# chiclet.net
KiCad netlist of a schematic drawn in EAGLE
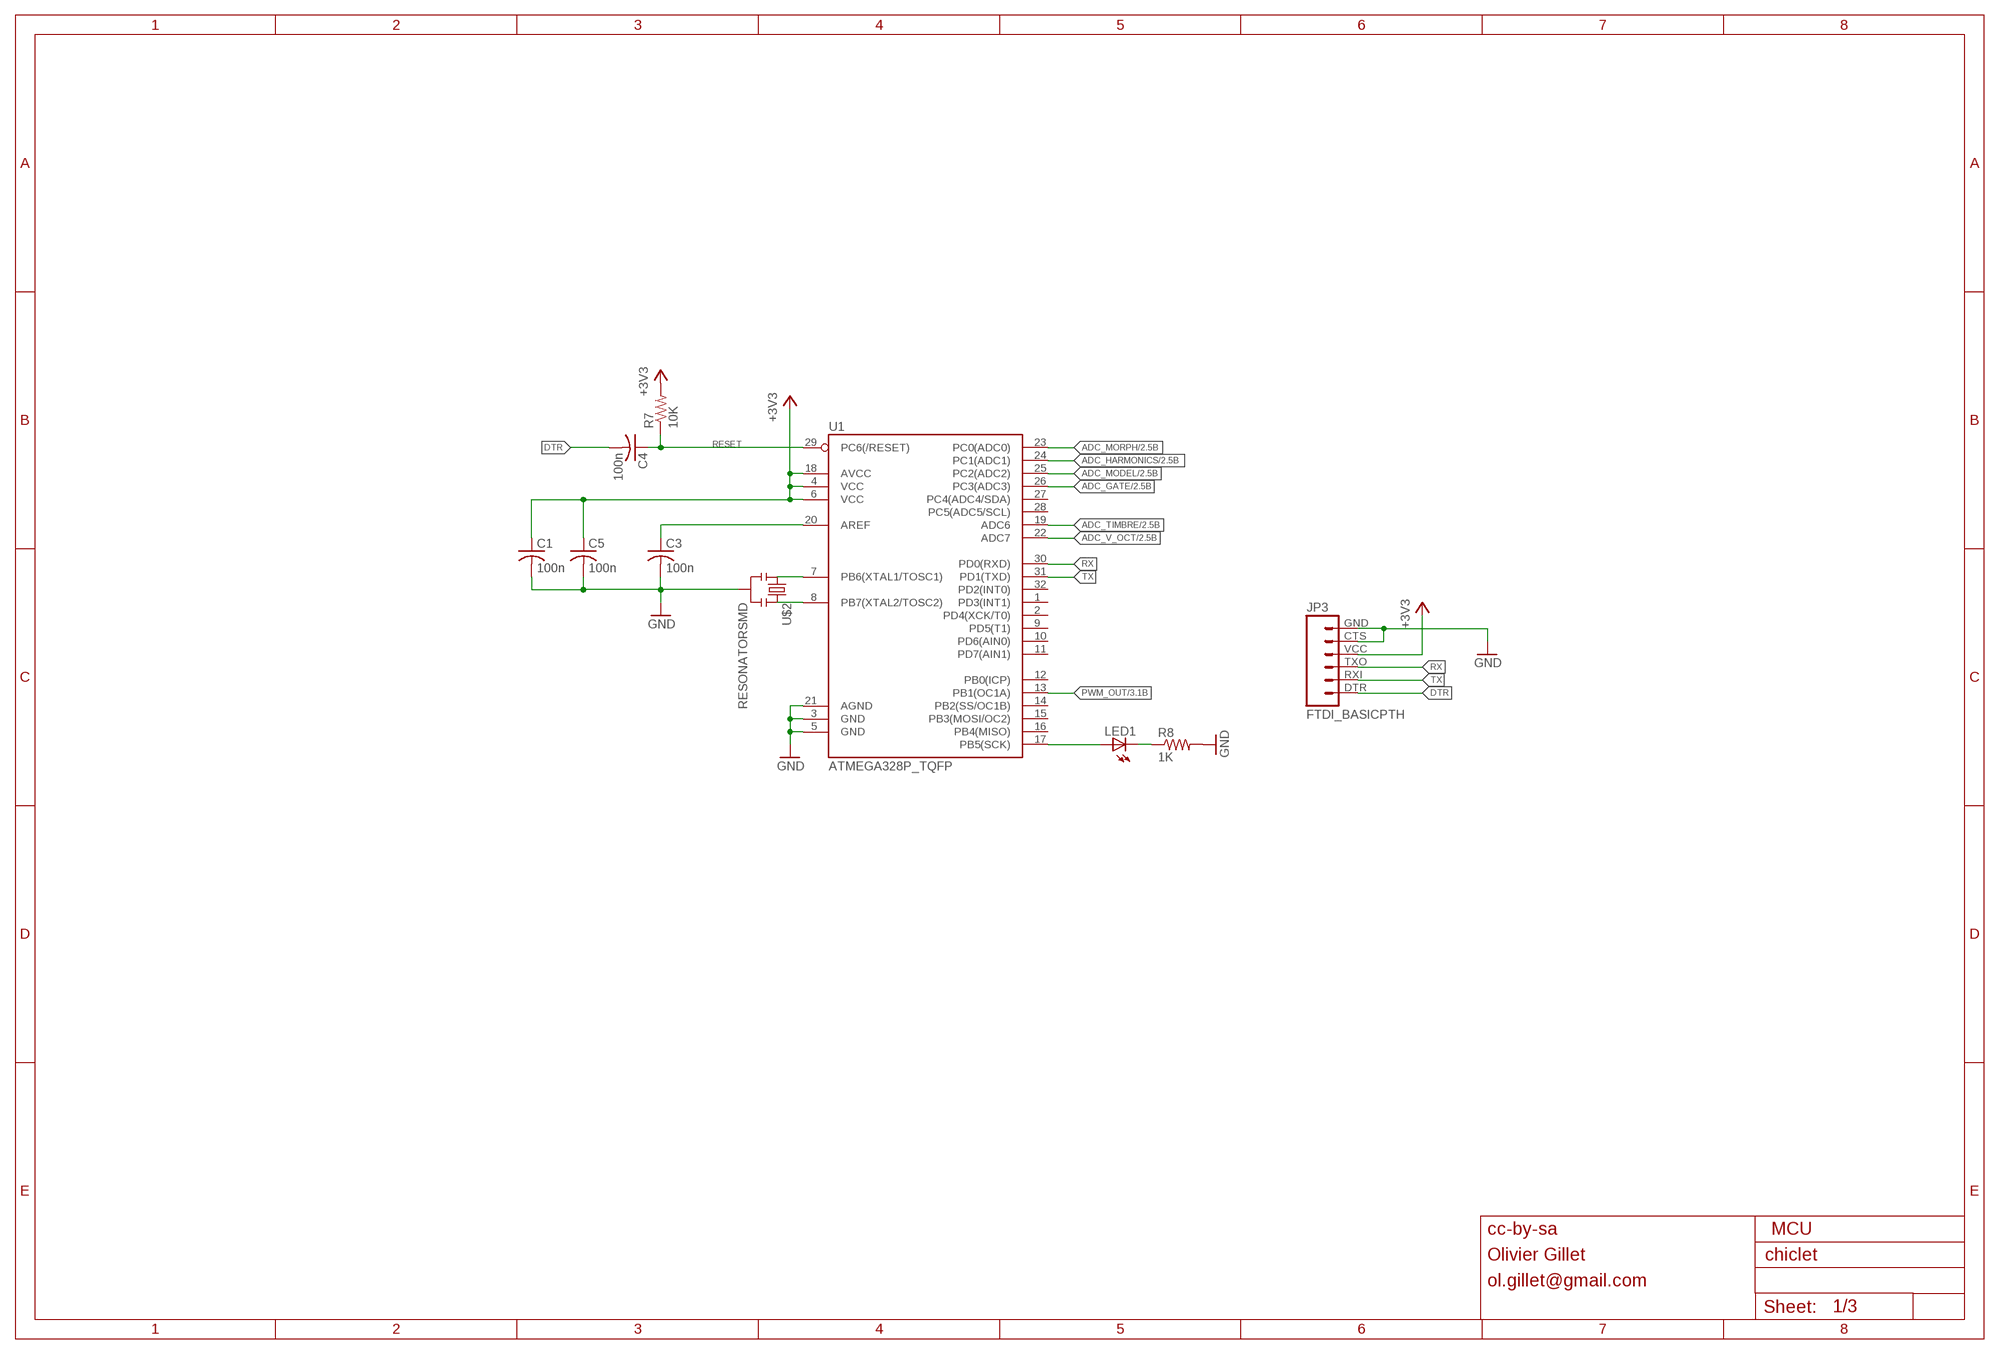
[diagram p0: schematic, sheet 1]
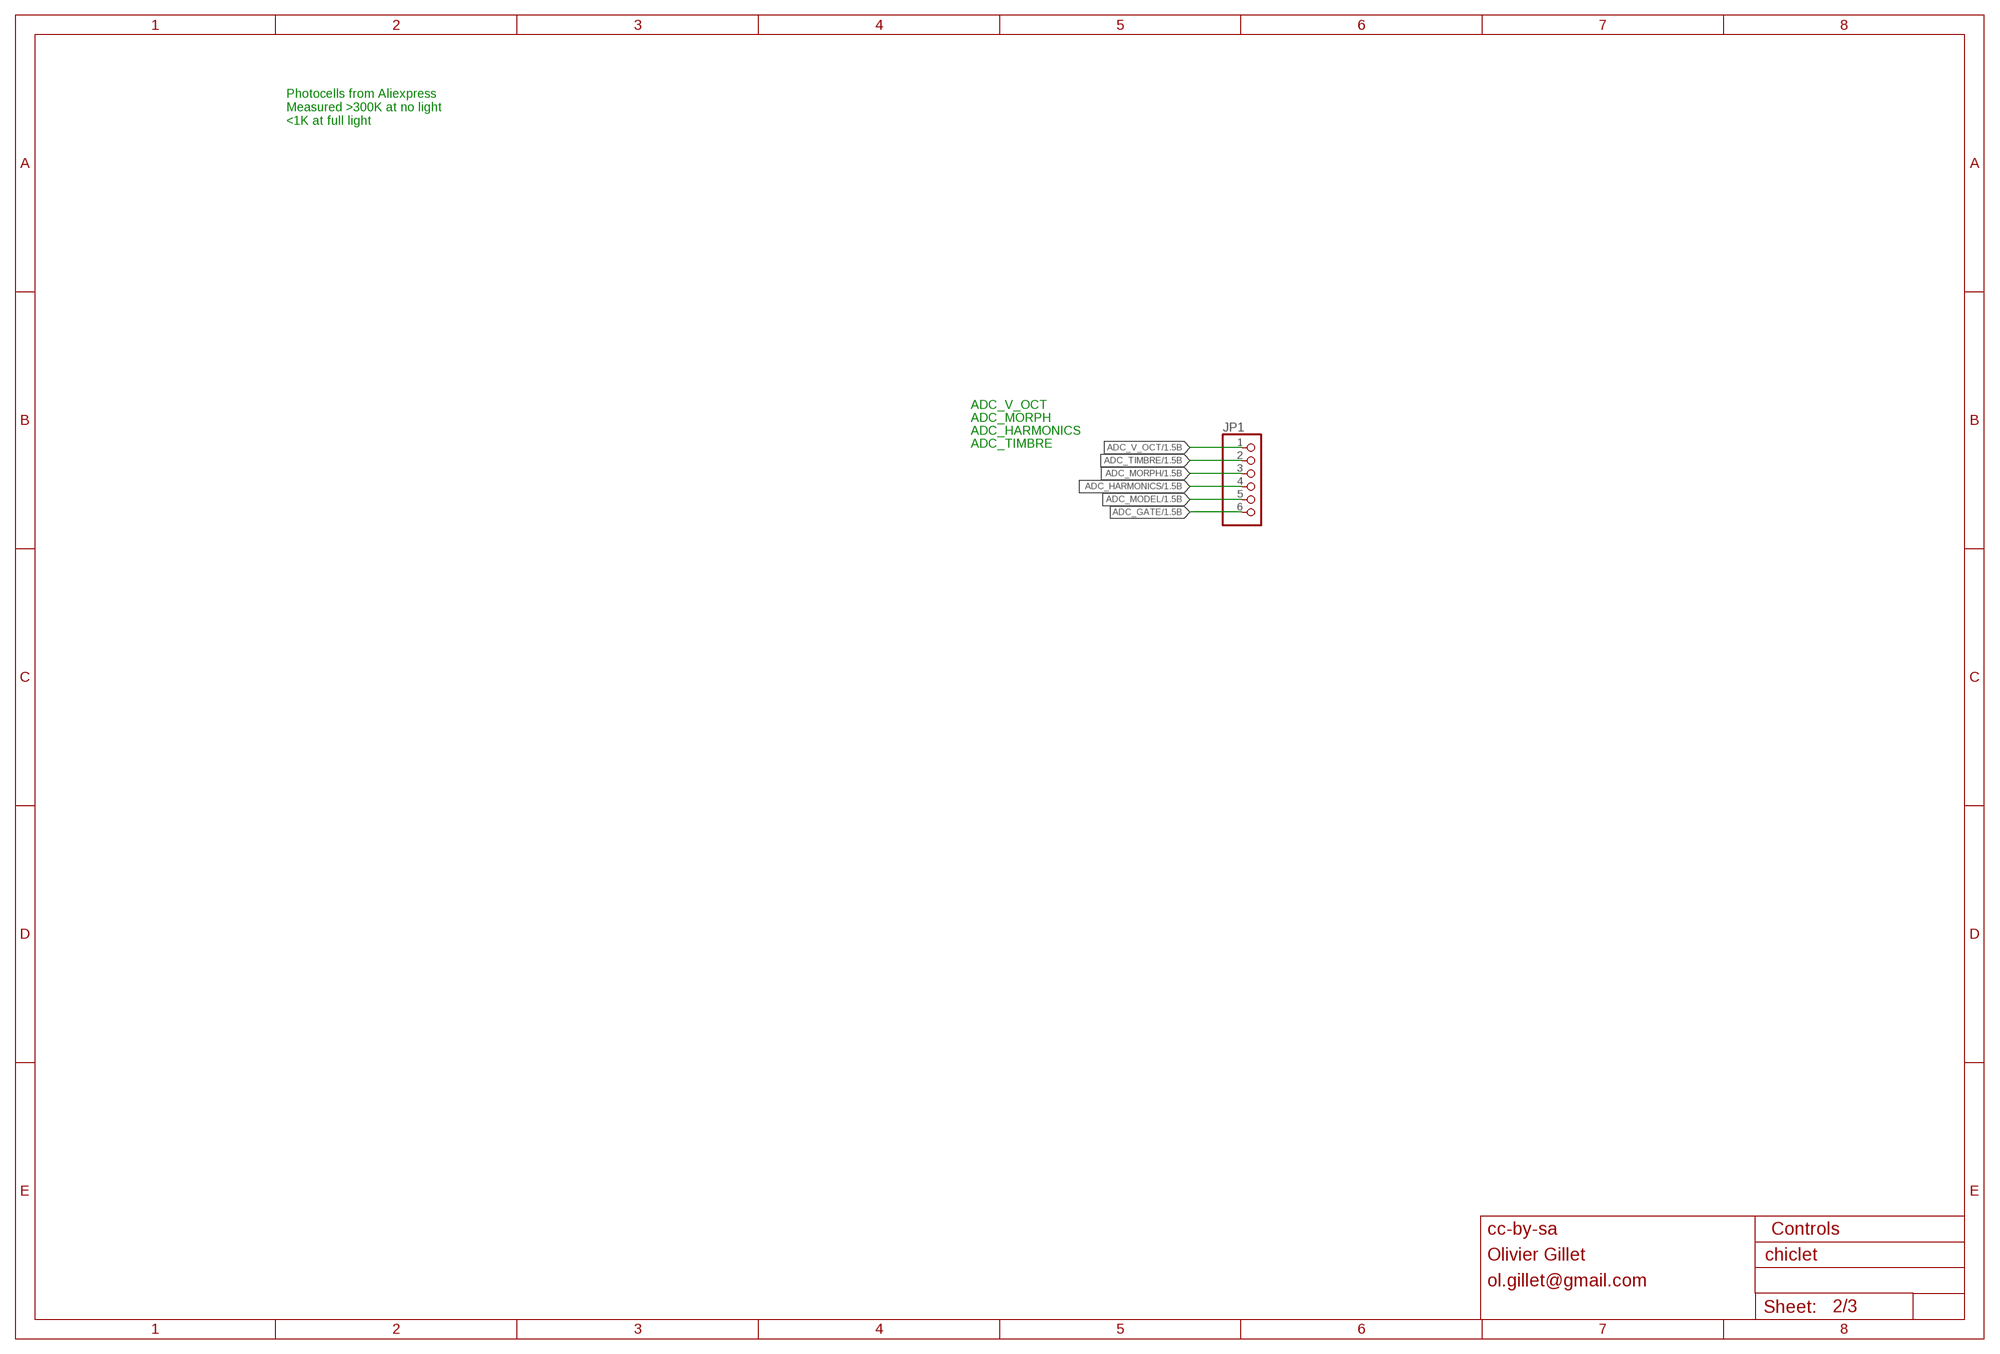
[diagram p1: schematic, sheet 2]
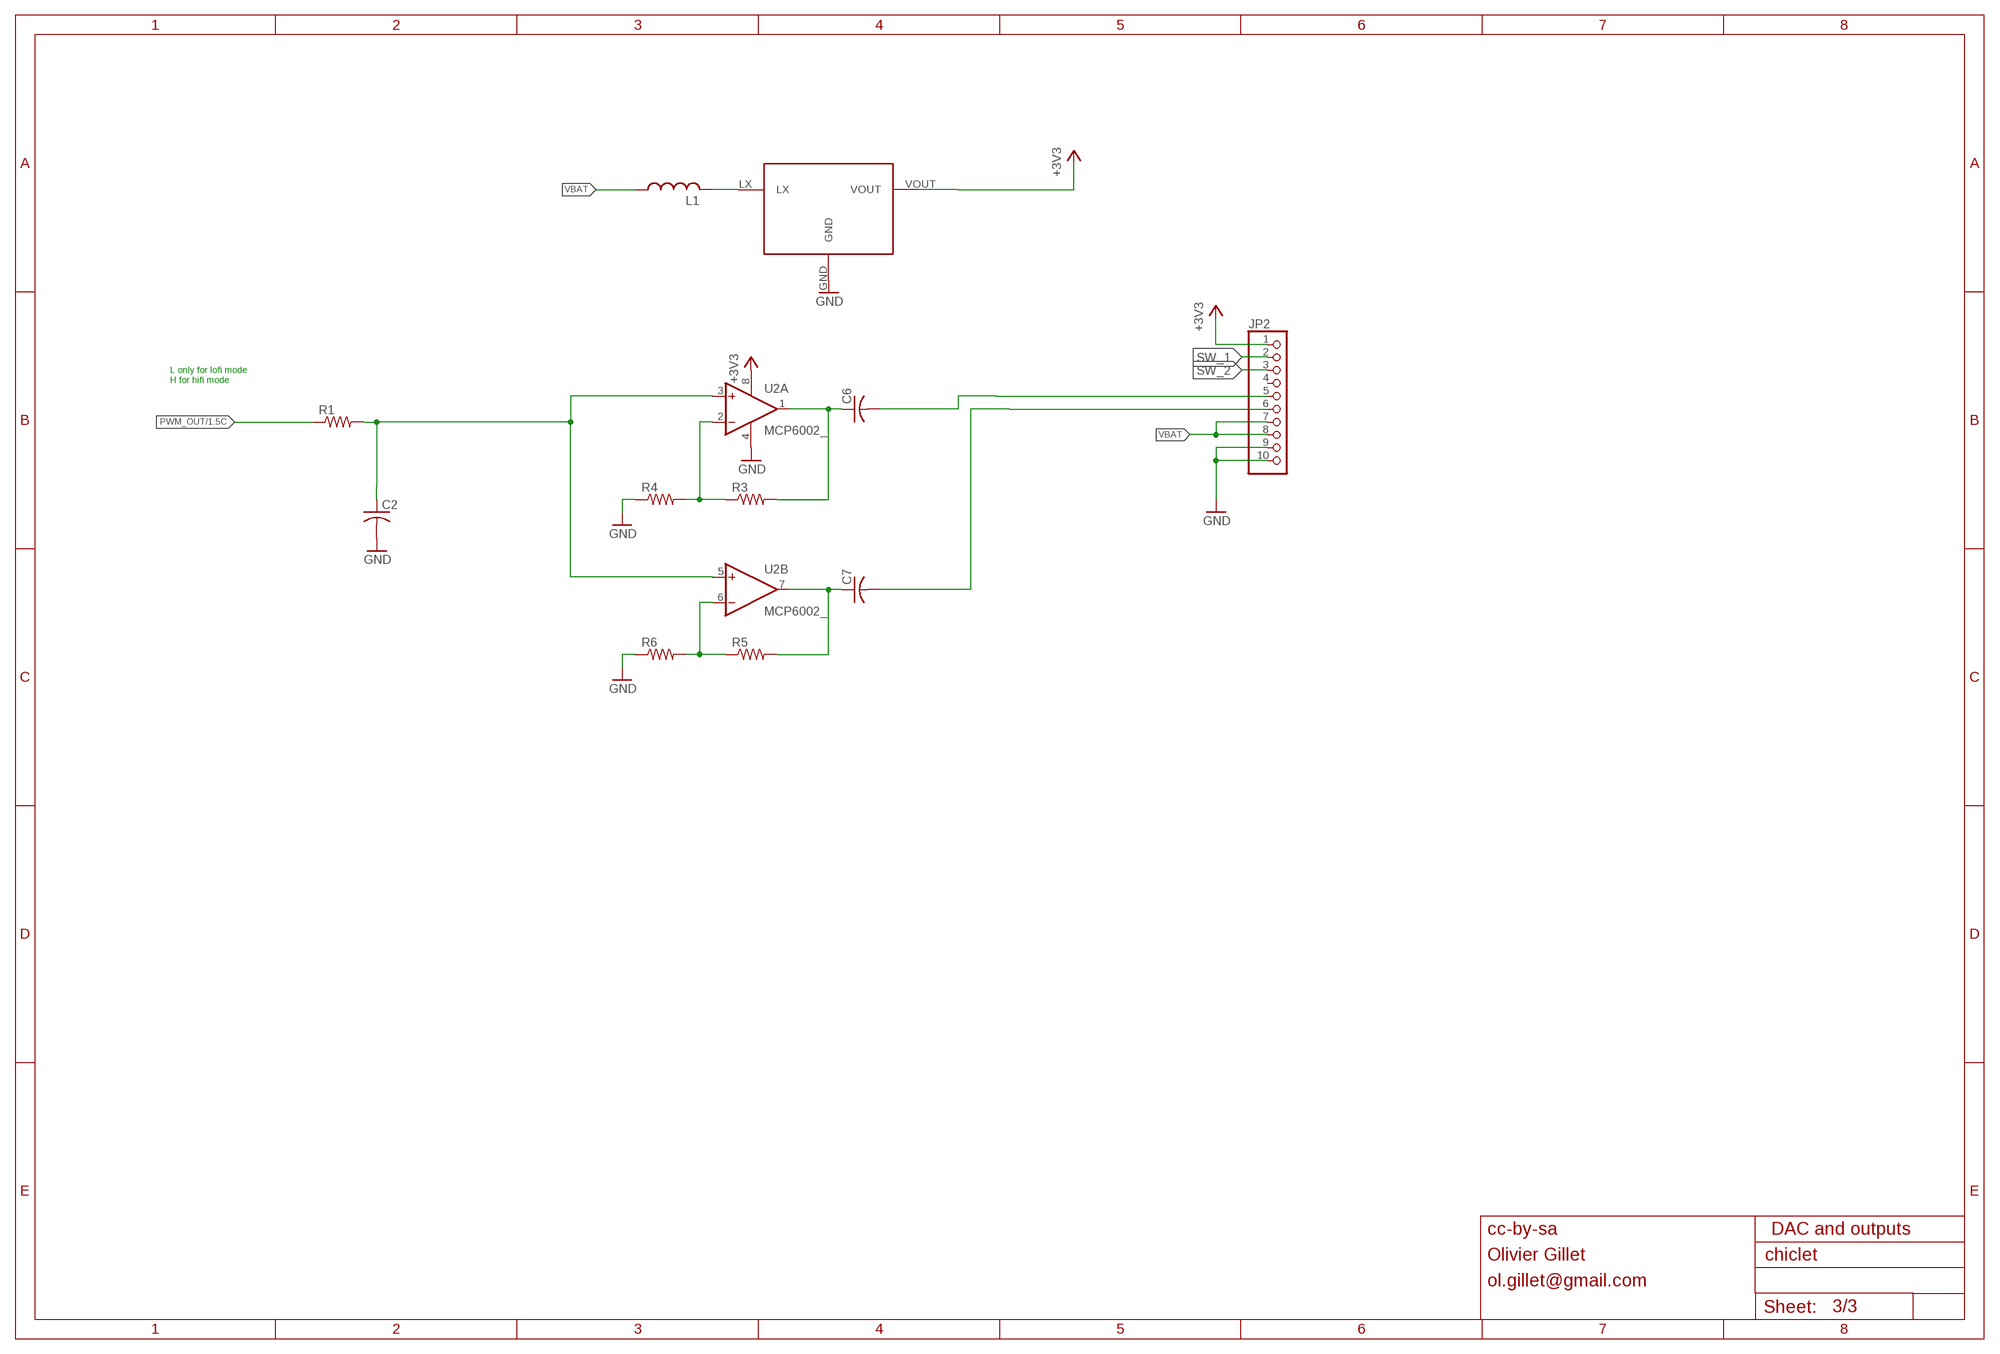
[diagram p2: schematic, sheet 3]

(export (version "E")
  (design (tool "Eeschema 10.0.6"))
  (components
    (comp (ref "C1")
      (value "100n")
      (footprint "eagle-import:C0805")
      (libsource (lib "eagle-import") (part "C-USC0805"))
    )
    (comp (ref "C3")
      (value "100n")
      (footprint "eagle-import:C0805")
      (libsource (lib "eagle-import") (part "C-USC0805"))
    )
    (comp (ref "C4")
      (value "100n")
      (footprint "eagle-import:C0805")
      (libsource (lib "eagle-import") (part "C-USC0805"))
    )
    (comp (ref "C5")
      (value "100n")
      (footprint "eagle-import:C0805")
      (libsource (lib "eagle-import") (part "C-USC0805"))
    )
    (comp (ref "JP3")
      (value "FTDI_BASICPTH")
      (footprint "eagle-import:FTDI_BASIC")
      (libsource (lib "eagle-import") (part "FTDI_BASICPTH"))
    )
    (comp (ref "LED1")
      (value "LED-0805")
      (footprint "eagle-import:LED-805")
      (libsource (lib "eagle-import") (part "LED-0805"))
    )
    (comp (ref "R7")
      (value "10K")
      (footprint "eagle-import:M0805")
      (libsource (lib "eagle-import") (part "R-US_M0805"))
    )
    (comp (ref "R8")
      (value "1K")
      (footprint "eagle-import:M0805")
      (libsource (lib "eagle-import") (part "R-US_M0805"))
    )
    (comp (ref "U$2")
      (value "RESONATORSMD")
      (footprint "eagle-import:RESONATOR-SMD")
      (libsource (lib "eagle-import") (part "RESONATORSMD"))
    )
    (comp (ref "U1")
      (value "ATMEGA328P_TQFP")
      (footprint "eagle-import:TQFP32-08")
      (libsource (lib "eagle-import") (part "ATMEGA328P_TQFP"))
    )
    (comp (ref "C2")
      (value "C-USC0805")
      (footprint "eagle-import:C0805")
      (libsource (lib "eagle-import") (part "C-USC0805"))
    )
    (comp (ref "C6")
      (value "C-USC0805")
      (footprint "eagle-import:C0805")
      (libsource (lib "eagle-import") (part "C-USC0805"))
    )
    (comp (ref "C7")
      (value "C-USC0805")
      (footprint "eagle-import:C0805")
      (libsource (lib "eagle-import") (part "C-USC0805"))
    )
    (comp (ref "JP2")
      (value "PINHD-1X10")
      (footprint "eagle-import:1X10")
      (libsource (lib "eagle-import") (part "PINHD-1X10"))
    )
    (comp (ref "L1")
      (value "L-USL2825P")
      (footprint "eagle-import:L2825P")
      (libsource (lib "eagle-import") (part "L-USL2825P"))
    )
    (comp (ref "R1")
      (value "R-US_R0805")
      (footprint "eagle-import:R0805")
      (libsource (lib "eagle-import") (part "R-US_R0805"))
    )
    (comp (ref "R3")
      (value "R-US_R0805")
      (footprint "eagle-import:R0805")
      (libsource (lib "eagle-import") (part "R-US_R0805"))
    )
    (comp (ref "R4")
      (value "R-US_R0805")
      (footprint "eagle-import:R0805")
      (libsource (lib "eagle-import") (part "R-US_R0805"))
    )
    (comp (ref "R5")
      (value "R-US_R0805")
      (footprint "eagle-import:R0805")
      (libsource (lib "eagle-import") (part "R-US_R0805"))
    )
    (comp (ref "R6")
      (value "R-US_R0805")
      (footprint "eagle-import:R0805")
      (libsource (lib "eagle-import") (part "R-US_R0805"))
    )
    (comp (ref "U$1")
      (value "QX2304L33E")
      (footprint "eagle-import:SOT89-R")
      (libsource (lib "eagle-import") (part "QX2304L33E"))
    )
    (comp (ref "U2")
      (value "MCP6002_")
      (footprint "eagle-import:SO08")
      (libsource (lib "eagle-import") (part "MCP6002_"))
    )
    (comp (ref "JP1")
      (value "PINHD-1X6")
      (footprint "eagle-import:1X06")
      (libsource (lib "eagle-import") (part "PINHD-1X6"))
    )
  )
  (nets
    (net (code "1") (name "+3V3") (class "Default")
      (node (ref "C1") (pin "1") (pinfunction "1_1") (pintype "passive"))
      (node (ref "C5") (pin "1") (pinfunction "1_1") (pintype "passive"))
      (node (ref "JP2") (pin "1") (pinfunction "1_1") (pintype "passive"))
      (node (ref "JP3") (pin "VCC") (pinfunction "4_VCC") (pintype "passive"))
      (node (ref "R7") (pin "2") (pinfunction "2_2") (pintype "passive"))
      (node (ref "U$1") (pin "VOUT") (pinfunction "VOUT_VOUT") (pintype "bidirectional"))
      (node (ref "U1") (pin "18") (pinfunction "AVCC_18") (pintype "bidirectional"))
      (node (ref "U1") (pin "4") (pinfunction "VCC_4") (pintype "bidirectional"))
      (node (ref "U1") (pin "6") (pinfunction "VCC_6") (pintype "bidirectional"))
      (node (ref "U2") (pin "8") (pinfunction "V+_8") (pintype "power_in"))
    )
    (net (code "2") (name "ADC_GATE") (class "Default")
      (node (ref "JP1") (pin "6") (pinfunction "6_6") (pintype "passive"))
      (node (ref "U1") (pin "26") (pinfunction "PC3(ADC3)_26") (pintype "bidirectional"))
    )
    (net (code "3") (name "ADC_HARMONICS") (class "Default")
      (node (ref "JP1") (pin "4") (pinfunction "4_4") (pintype "passive"))
      (node (ref "U1") (pin "24") (pinfunction "PC1(ADC1)_24") (pintype "bidirectional"))
    )
    (net (code "4") (name "ADC_MODEL") (class "Default")
      (node (ref "JP1") (pin "5") (pinfunction "5_5") (pintype "passive"))
      (node (ref "U1") (pin "25") (pinfunction "PC2(ADC2)_25") (pintype "bidirectional"))
    )
    (net (code "5") (name "ADC_MORPH") (class "Default")
      (node (ref "JP1") (pin "3") (pinfunction "3_3") (pintype "passive"))
      (node (ref "U1") (pin "23") (pinfunction "PC0(ADC0)_23") (pintype "bidirectional"))
    )
    (net (code "6") (name "ADC_TIMBRE") (class "Default")
      (node (ref "JP1") (pin "2") (pinfunction "2_2") (pintype "passive"))
      (node (ref "U1") (pin "19") (pinfunction "ADC6_19") (pintype "bidirectional"))
    )
    (net (code "7") (name "ADC_V_OCT") (class "Default")
      (node (ref "JP1") (pin "1") (pinfunction "1_1") (pintype "passive"))
      (node (ref "U1") (pin "22") (pinfunction "ADC7_22") (pintype "bidirectional"))
    )
    (net (code "8") (name "DTR") (class "Default")
      (node (ref "C4") (pin "2") (pinfunction "2_2") (pintype "passive"))
      (node (ref "JP3") (pin "DTR") (pinfunction "1_DTR") (pintype "passive"))
    )
    (net (code "9") (name "GND") (class "Default")
      (node (ref "C1") (pin "2") (pinfunction "2_2") (pintype "passive"))
      (node (ref "C2") (pin "2") (pinfunction "2_2") (pintype "passive"))
      (node (ref "C3") (pin "2") (pinfunction "2_2") (pintype "passive"))
      (node (ref "C5") (pin "2") (pinfunction "2_2") (pintype "passive"))
      (node (ref "JP2") (pin "10") (pinfunction "10_10") (pintype "passive"))
      (node (ref "JP2") (pin "9") (pinfunction "9_9") (pintype "passive"))
      (node (ref "JP3") (pin "CTS") (pinfunction "5_CTS") (pintype "passive"))
      (node (ref "JP3") (pin "GND") (pinfunction "6_GND") (pintype "passive"))
      (node (ref "R4") (pin "1") (pinfunction "1_1") (pintype "passive"))
      (node (ref "R6") (pin "1") (pinfunction "1_1") (pintype "passive"))
      (node (ref "R8") (pin "2") (pinfunction "2_2") (pintype "passive"))
      (node (ref "U$1") (pin "GND") (pinfunction "GND_GND") (pintype "bidirectional"))
      (node (ref "U$2") (pin "2") (pinfunction "2_2") (pintype "passive"))
      (node (ref "U1") (pin "21") (pinfunction "AGND_21") (pintype "bidirectional"))
      (node (ref "U1") (pin "3") (pinfunction "GND_3") (pintype "bidirectional"))
      (node (ref "U1") (pin "5") (pinfunction "GND_5") (pintype "bidirectional"))
      (node (ref "U2") (pin "4") (pinfunction "V-_4") (pintype "power_in"))
    )
    (net (code "10") (name "Net-(C6-Pad2)") (class "Default")
      (node (ref "C6") (pin "2") (pinfunction "2_2") (pintype "passive"))
      (node (ref "JP2") (pin "5") (pinfunction "5_5") (pintype "passive"))
    )
    (net (code "11") (name "Net-(C7-Pad2)") (class "Default")
      (node (ref "C7") (pin "2") (pinfunction "2_2") (pintype "passive"))
      (node (ref "JP2") (pin "6") (pinfunction "6_6") (pintype "passive"))
    )
    (net (code "12") (name "Net-(L1-Pad2)") (class "Default")
      (node (ref "L1") (pin "2") (pinfunction "2_2") (pintype "passive"))
      (node (ref "U$1") (pin "LX") (pinfunction "LX_LX") (pintype "bidirectional"))
    )
    (net (code "13") (name "Net-(LED1-PadC)") (class "Default")
      (node (ref "LED1") (pin "C") (pinfunction "C_C") (pintype "passive"))
      (node (ref "R8") (pin "1") (pinfunction "1_1") (pintype "passive"))
    )
    (net (code "14") (name "Net-(U1-AREF)") (class "Default")
      (node (ref "C3") (pin "1") (pinfunction "1_1") (pintype "passive"))
      (node (ref "U1") (pin "20") (pinfunction "AREF_20") (pintype "bidirectional"))
    )
    (net (code "15") (name "Net-(U1-PB5(SCK))") (class "Default")
      (node (ref "LED1") (pin "A") (pinfunction "A_A") (pintype "passive"))
      (node (ref "U1") (pin "17") (pinfunction "PB5(SCK)_17") (pintype "bidirectional"))
    )
    (net (code "16") (name "Net-(U1-PB6(XTAL1{slash}TOSC1))") (class "Default")
      (node (ref "U$2") (pin "1") (pinfunction "1_1") (pintype "passive"))
      (node (ref "U1") (pin "7") (pinfunction "PB6(XTAL1/TOSC1)_7") (pintype "bidirectional"))
    )
    (net (code "17") (name "Net-(U1-PB7(XTAL2{slash}TOSC2))") (class "Default")
      (node (ref "U$2") (pin "3") (pinfunction "3_3") (pintype "passive"))
      (node (ref "U1") (pin "8") (pinfunction "PB7(XTAL2/TOSC2)_8") (pintype "bidirectional"))
    )
    (net (code "18") (name "Net-(U2A-+IN)") (class "Default")
      (node (ref "C2") (pin "1") (pinfunction "1_1") (pintype "passive"))
      (node (ref "R1") (pin "2") (pinfunction "2_2") (pintype "passive"))
      (node (ref "U2") (pin "3") (pinfunction "+IN_3") (pintype "input"))
      (node (ref "U2") (pin "5") (pinfunction "+IN_5") (pintype "input"))
    )
    (net (code "19") (name "Net-(U2A--IN)") (class "Default")
      (node (ref "R3") (pin "1") (pinfunction "1_1") (pintype "passive"))
      (node (ref "R4") (pin "2") (pinfunction "2_2") (pintype "passive"))
      (node (ref "U2") (pin "2") (pinfunction "-IN_2") (pintype "input"))
    )
    (net (code "20") (name "Net-(U2A-OUT)") (class "Default")
      (node (ref "C6") (pin "1") (pinfunction "1_1") (pintype "passive"))
      (node (ref "R3") (pin "2") (pinfunction "2_2") (pintype "passive"))
      (node (ref "U2") (pin "1") (pinfunction "OUT_1") (pintype "output"))
    )
    (net (code "21") (name "Net-(U2B--IN)") (class "Default")
      (node (ref "R5") (pin "1") (pinfunction "1_1") (pintype "passive"))
      (node (ref "R6") (pin "2") (pinfunction "2_2") (pintype "passive"))
      (node (ref "U2") (pin "6") (pinfunction "-IN_6") (pintype "input"))
    )
    (net (code "22") (name "Net-(U2B-OUT)") (class "Default")
      (node (ref "C7") (pin "1") (pinfunction "1_1") (pintype "passive"))
      (node (ref "R5") (pin "2") (pinfunction "2_2") (pintype "passive"))
      (node (ref "U2") (pin "7") (pinfunction "OUT_7") (pintype "output"))
    )
    (net (code "23") (name "PWM_OUT") (class "Default")
      (node (ref "R1") (pin "1") (pinfunction "1_1") (pintype "passive"))
      (node (ref "U1") (pin "13") (pinfunction "PB1(OC1A)_13") (pintype "bidirectional"))
    )
    (net (code "24") (name "RESET") (class "Default")
      (node (ref "C4") (pin "1") (pinfunction "1_1") (pintype "passive"))
      (node (ref "R7") (pin "1") (pinfunction "1_1") (pintype "passive"))
      (node (ref "U1") (pin "29") (pinfunction "PC6(/RESET)_29") (pintype "bidirectional"))
    )
    (net (code "25") (name "RX") (class "Default")
      (node (ref "JP3") (pin "TXO") (pinfunction "3_TXO") (pintype "passive"))
      (node (ref "U1") (pin "30") (pinfunction "PD0(RXD)_30") (pintype "bidirectional"))
    )
    (net (code "26") (name "SW_1") (class "Default")
      (node (ref "JP2") (pin "2") (pinfunction "2_2") (pintype "passive"))
    )
    (net (code "27") (name "SW_2") (class "Default")
      (node (ref "JP2") (pin "3") (pinfunction "3_3") (pintype "passive"))
    )
    (net (code "28") (name "TX") (class "Default")
      (node (ref "JP3") (pin "RXI") (pinfunction "2_RXI") (pintype "passive"))
      (node (ref "U1") (pin "31") (pinfunction "PD1(TXD)_31") (pintype "bidirectional"))
    )
    (net (code "29") (name "VBAT") (class "Default")
      (node (ref "JP2") (pin "7") (pinfunction "7_7") (pintype "passive"))
      (node (ref "JP2") (pin "8") (pinfunction "8_8") (pintype "passive"))
      (node (ref "L1") (pin "1") (pinfunction "1_1") (pintype "passive"))
    )
    (net (code "30") (name "unconnected-(JP2-Pad4)") (class "Default")
      (node (ref "JP2") (pin "4") (pinfunction "4_4") (pintype "passive"))
    )
    (net (code "31") (name "unconnected-(U1-PB0(ICP)-Pad12)") (class "Default")
      (node (ref "U1") (pin "12") (pinfunction "PB0(ICP)_12") (pintype "bidirectional"))
    )
    (net (code "32") (name "unconnected-(U1-PB2(SS{slash}OC1B)-Pad14)") (class "Default")
      (node (ref "U1") (pin "14") (pinfunction "PB2(SS/OC1B)_14") (pintype "bidirectional"))
    )
    (net (code "33") (name "unconnected-(U1-PB3(MOSI{slash}OC2)-Pad15)") (class "Default")
      (node (ref "U1") (pin "15") (pinfunction "PB3(MOSI/OC2)_15") (pintype "bidirectional"))
    )
    (net (code "34") (name "unconnected-(U1-PB4(MISO)-Pad16)") (class "Default")
      (node (ref "U1") (pin "16") (pinfunction "PB4(MISO)_16") (pintype "bidirectional"))
    )
    (net (code "35") (name "unconnected-(U1-PC4(ADC4{slash}SDA)-Pad27)") (class "Default")
      (node (ref "U1") (pin "27") (pinfunction "PC4(ADC4/SDA)_27") (pintype "bidirectional"))
    )
    (net (code "36") (name "unconnected-(U1-PC5(ADC5{slash}SCL)-Pad28)") (class "Default")
      (node (ref "U1") (pin "28") (pinfunction "PC5(ADC5/SCL)_28") (pintype "bidirectional"))
    )
    (net (code "37") (name "unconnected-(U1-PD2(INT0)-Pad32)") (class "Default")
      (node (ref "U1") (pin "32") (pinfunction "PD2(INT0)_32") (pintype "bidirectional"))
    )
    (net (code "38") (name "unconnected-(U1-PD3(INT1)-Pad1)") (class "Default")
      (node (ref "U1") (pin "1") (pinfunction "PD3(INT1)_1") (pintype "bidirectional"))
    )
    (net (code "39") (name "unconnected-(U1-PD4(XCK{slash}T0)-Pad2)") (class "Default")
      (node (ref "U1") (pin "2") (pinfunction "PD4(XCK/T0)_2") (pintype "bidirectional"))
    )
    (net (code "40") (name "unconnected-(U1-PD5(T1)-Pad9)") (class "Default")
      (node (ref "U1") (pin "9") (pinfunction "PD5(T1)_9") (pintype "bidirectional"))
    )
    (net (code "41") (name "unconnected-(U1-PD6(AIN0)-Pad10)") (class "Default")
      (node (ref "U1") (pin "10") (pinfunction "PD6(AIN0)_10") (pintype "bidirectional"))
    )
    (net (code "42") (name "unconnected-(U1-PD7(AIN1)-Pad11)") (class "Default")
      (node (ref "U1") (pin "11") (pinfunction "PD7(AIN1)_11") (pintype "bidirectional"))
    )
  )
)
